# Power.net
KiCad netlist of a schematic drawn in Altium Designer
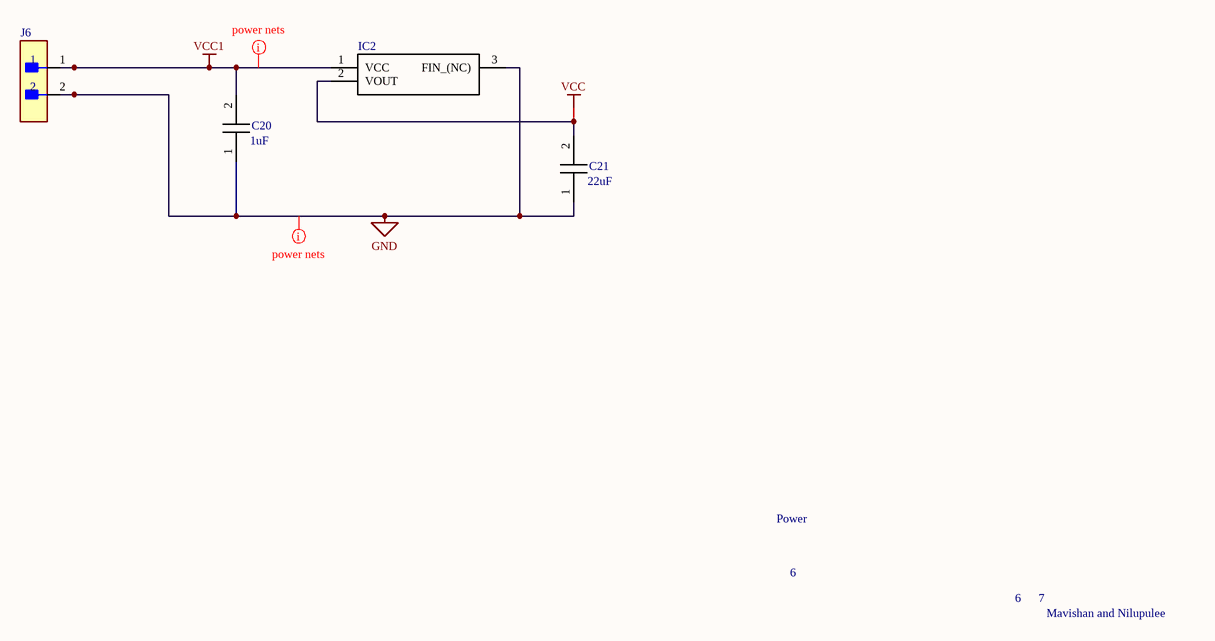
[diagram p0: Power.SchDoc]

(export (version "E")
  (design (tool "Eeschema 10.0.6"))
  (components
    (comp (ref "C20")
      (value "12063C105MAT2A")
      (footprint "SamacSys:CAPC3216X178N")
      (description "Capacitor")
      (fields (field (name "MOUSER PART NUMBER") "581-12063C105MAT2A") (field (name "PARAMETER 1") "1uF"))
      (libsource (lib "*") (part "12063C105MAT2A"))
    )
    (comp (ref "C21")
      (value "12063D226MAT2A")
      (footprint "SamacSys:CAPC3216X229N")
      (description "Capacitor")
      (fields (field (name "MOUSER PART NUMBER") "581-12063D226MAT2A") (field (name "PARAMETER 1") "22uF"))
      (libsource (lib "*") (part "12063D226MAT2A"))
    )
    (comp (ref "IC2")
      (value "BD450M5FP-CE2")
      (footprint "SamacSys:ROHM_TO-252-3")
      (description "Integrated Circuit")
      (fields (field (name "MOUSER PART NUMBER") "755-BD450M5FP-CE2"))
      (libsource (lib "*") (part "BD450M5FP-CE2"))
    )
    (comp (ref "J6")
      (value "B2B-XH-A(LF)(SN)")
      (footprint "FP-B2B-XH-A_LF_SN-MFG")
      (description "CONN HEADER VERT 2POS 2.5MM")
      (libsource (lib "Altium Content Vault") (part "3bc925449376181038e59eaffc5286c"))
    )
  )
  (nets
    (net (code "1") (name "GND") (class "Default")
      (node (ref "C20") (pin "1") (pinfunction "1_1") (pintype "passive"))
      (node (ref "C21") (pin "1") (pinfunction "1_1") (pintype "passive"))
      (node (ref "IC2") (pin "3") (pinfunction "FIN_(NC)_3") (pintype "passive"))
      (node (ref "J6") (pin "2") (pinfunction "2_2") (pintype "passive"))
    )
    (net (code "2") (name "VCC") (class "Default")
      (node (ref "C21") (pin "2") (pinfunction "2_2") (pintype "passive"))
      (node (ref "IC2") (pin "2") (pinfunction "VOUT_2") (pintype "passive"))
    )
    (net (code "3") (name "VCC1") (class "Default")
      (node (ref "C20") (pin "2") (pinfunction "2_2") (pintype "passive"))
      (node (ref "IC2") (pin "1") (pinfunction "VCC_1") (pintype "passive"))
      (node (ref "J6") (pin "1") (pinfunction "1_1") (pintype "passive"))
    )
  )
)
